# SCH_MinkyBoard_2025-11-26.net
KiCad netlist of a schematic drawn in EasyEDA
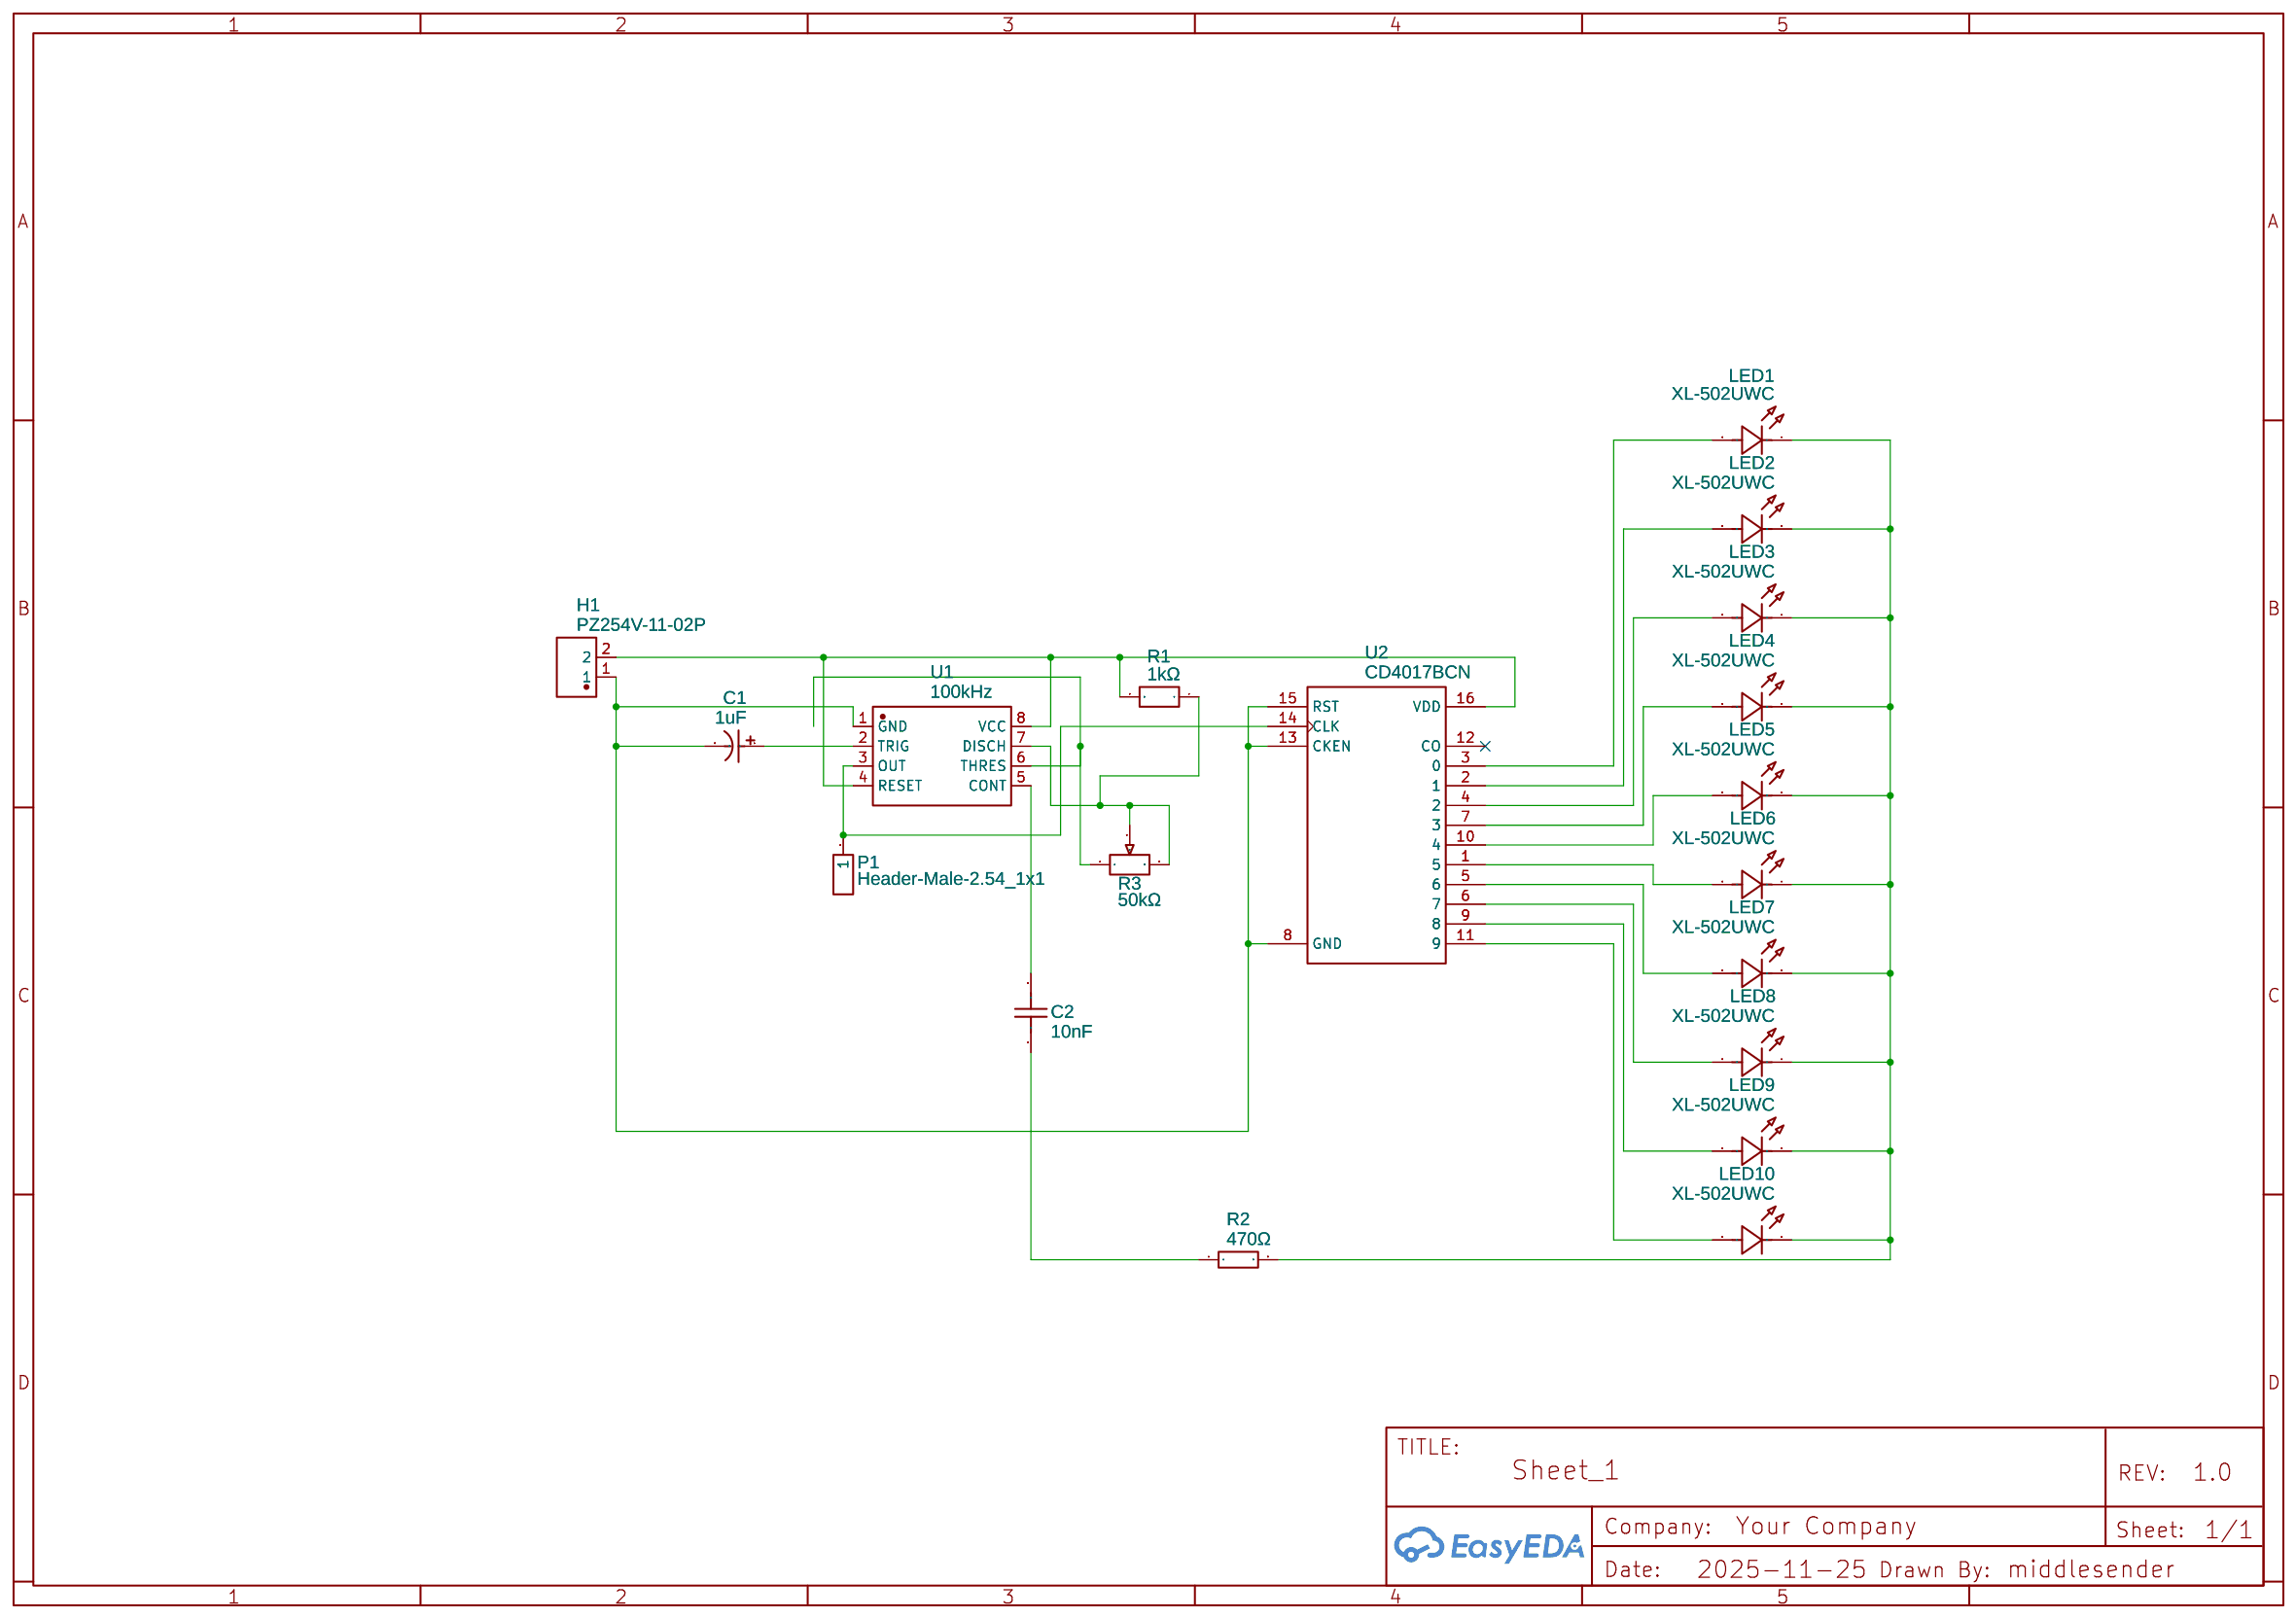
[diagram p0: schematic sheet]

(export (version "E")
  (design (tool "Eeschema 10.0.6"))
  (components
    (comp (ref "C1")
      (value "1uF")
      (fields (field (name "Manufacturer Part") "KF010M050C110A") (field (name "Manufacturer") "CapXon(丰宾)"))
      (libsource (lib "") (part "KF010M050C110A"))
    )
    (comp (ref "C2")
      (value "10nF")
      (fields (field (name "Manufacturer Part") "N09F1B103MN0B0S0N0") (field (name "Manufacturer") "STE(松田)"))
      (libsource (lib "") (part "N09F1B103MN0B0S0N0"))
    )
    (comp (ref "H1")
      (value "PZ254V-11-02P")
      (fields (field (name "Manufacturer") "XFCN(兴飞)"))
      (libsource (lib "") (part "PZ254V-11-02P"))
    )
    (comp (ref "LED1")
      (value "XL-502UWC")
      (fields (field (name "Manufacturer") "XINGLIGHT(成兴光)"))
      (libsource (lib "") (part "XL-502UWC"))
    )
    (comp (ref "LED2")
      (value "XL-502UWC")
      (fields (field (name "Manufacturer") "XINGLIGHT(成兴光)"))
      (libsource (lib "") (part "XL-502UWC"))
    )
    (comp (ref "LED3")
      (value "XL-502UWC")
      (fields (field (name "Manufacturer") "XINGLIGHT(成兴光)"))
      (libsource (lib "") (part "XL-502UWC"))
    )
    (comp (ref "LED4")
      (value "XL-502UWC")
      (fields (field (name "Manufacturer") "XINGLIGHT(成兴光)"))
      (libsource (lib "") (part "XL-502UWC"))
    )
    (comp (ref "LED5")
      (value "XL-502UWC")
      (fields (field (name "Manufacturer") "XINGLIGHT(成兴光)"))
      (libsource (lib "") (part "XL-502UWC"))
    )
    (comp (ref "LED6")
      (value "XL-502UWC")
      (fields (field (name "Manufacturer") "XINGLIGHT(成兴光)"))
      (libsource (lib "") (part "XL-502UWC"))
    )
    (comp (ref "LED7")
      (value "XL-502UWC")
      (fields (field (name "Manufacturer") "XINGLIGHT(成兴光)"))
      (libsource (lib "") (part "XL-502UWC"))
    )
    (comp (ref "LED8")
      (value "XL-502UWC")
      (fields (field (name "Manufacturer") "XINGLIGHT(成兴光)"))
      (libsource (lib "") (part "XL-502UWC"))
    )
    (comp (ref "LED9")
      (value "XL-502UWC")
      (fields (field (name "Manufacturer") "XINGLIGHT(成兴光)"))
      (libsource (lib "") (part "XL-502UWC"))
    )
    (comp (ref "LED10")
      (value "XL-502UWC")
      (fields (field (name "Manufacturer") "XINGLIGHT(成兴光)"))
      (libsource (lib "") (part "XL-502UWC"))
    )
    (comp (ref "P1")
      (value "Header-Male-2.54_1x1")
      (fields (field (name "Manufacturer Part") "2.54-1*1P针") (field (name "Manufacturer") "BOOMELE(博穆精密)"))
      (libsource (lib "") (part "Header-Male-2.54_1x1"))
    )
    (comp (ref "R1")
      (value "1kΩ")
      (fields (field (name "Manufacturer Part") "MF1/4W-1KΩ±1%T52") (field (name "Manufacturer") "华星机电"))
      (libsource (lib "") (part "MF1/4W-1KΩ±1%T52"))
    )
    (comp (ref "R2")
      (value "470Ω")
      (fields
        (field (name "Manufacturer Part") "MFR0W4F4700A50")
        (field (name "Manufacturer") "UNI-ROYAL(厚声)")
      )
      (libsource (lib "") (part "MFR0W4F4700A50"))
    )
    (comp (ref "R3")
      (value "50kΩ")
      (fields (field (name "Manufacturer Part") "3296X-1-503") (field (name "Manufacturer") "BOCHEN(博晨)"))
      (libsource (lib "") (part "3296X-1-503_C118912"))
    )
    (comp (ref "U1")
      (value "100kHz")
      (fields (field (name "Manufacturer Part") "NE555P") (field (name "Manufacturer") "TI(德州仪器)"))
      (libsource (lib "") (part "NE555P"))
    )
    (comp (ref "U2") (value "CD4017BCN") (libsource (lib "") (part "CD4017BCN")))
  )
  (nets
    (net (code "1") (name "Net-(C2-Pad1)") (class "Default")
      (node (ref "C2") (pin "1") (pinfunction "1_1") (pintype "unspecified"))
      (node (ref "R2") (pin "1") (pinfunction "1_1") (pintype "input"))
    )
    (net (code "2") (name "Net-(LED1-A)") (class "Default")
      (node (ref "LED1") (pin "2") (pinfunction "A_2") (pintype "unspecified"))
      (node (ref "U2") (pin "3") (pinfunction "0_3") (pintype "output"))
    )
    (net (code "3") (name "Net-(LED1-K)") (class "Default")
      (node (ref "LED1") (pin "1") (pinfunction "K_1") (pintype "unspecified"))
      (node (ref "LED10") (pin "1") (pinfunction "K_1") (pintype "unspecified"))
      (node (ref "LED2") (pin "1") (pinfunction "K_1") (pintype "unspecified"))
      (node (ref "LED3") (pin "1") (pinfunction "K_1") (pintype "unspecified"))
      (node (ref "LED4") (pin "1") (pinfunction "K_1") (pintype "unspecified"))
      (node (ref "LED5") (pin "1") (pinfunction "K_1") (pintype "unspecified"))
      (node (ref "LED6") (pin "1") (pinfunction "K_1") (pintype "unspecified"))
      (node (ref "LED7") (pin "1") (pinfunction "K_1") (pintype "unspecified"))
      (node (ref "LED8") (pin "1") (pinfunction "K_1") (pintype "unspecified"))
      (node (ref "LED9") (pin "1") (pinfunction "K_1") (pintype "unspecified"))
      (node (ref "R2") (pin "2") (pinfunction "2_2") (pintype "input"))
    )
    (net (code "4") (name "Net-(LED2-A)") (class "Default")
      (node (ref "LED2") (pin "2") (pinfunction "A_2") (pintype "unspecified"))
      (node (ref "U2") (pin "2") (pinfunction "1_2") (pintype "output"))
    )
    (net (code "5") (name "Net-(LED3-A)") (class "Default")
      (node (ref "LED3") (pin "2") (pinfunction "A_2") (pintype "unspecified"))
      (node (ref "U2") (pin "4") (pinfunction "2_4") (pintype "output"))
    )
    (net (code "6") (name "Net-(LED4-A)") (class "Default")
      (node (ref "LED4") (pin "2") (pinfunction "A_2") (pintype "unspecified"))
      (node (ref "U2") (pin "7") (pinfunction "3_7") (pintype "output"))
    )
    (net (code "7") (name "Net-(LED5-A)") (class "Default")
      (node (ref "LED5") (pin "2") (pinfunction "A_2") (pintype "unspecified"))
      (node (ref "U2") (pin "10") (pinfunction "4_10") (pintype "output"))
    )
    (net (code "8") (name "Net-(LED6-A)") (class "Default")
      (node (ref "LED6") (pin "2") (pinfunction "A_2") (pintype "unspecified"))
      (node (ref "U2") (pin "1") (pinfunction "5_1") (pintype "output"))
    )
    (net (code "9") (name "Net-(LED7-A)") (class "Default")
      (node (ref "LED7") (pin "2") (pinfunction "A_2") (pintype "unspecified"))
      (node (ref "U2") (pin "5") (pinfunction "6_5") (pintype "output"))
    )
    (net (code "10") (name "Net-(LED8-A)") (class "Default")
      (node (ref "LED8") (pin "2") (pinfunction "A_2") (pintype "unspecified"))
      (node (ref "U2") (pin "6") (pinfunction "7_6") (pintype "output"))
    )
    (net (code "11") (name "Net-(LED9-A)") (class "Default")
      (node (ref "LED9") (pin "2") (pinfunction "A_2") (pintype "unspecified"))
      (node (ref "U2") (pin "9") (pinfunction "8_9") (pintype "output"))
    )
    (net (code "12") (name "Net-(LED10-A)") (class "Default")
      (node (ref "LED10") (pin "2") (pinfunction "A_2") (pintype "unspecified"))
      (node (ref "U2") (pin "11") (pinfunction "9_11") (pintype "output"))
    )
    (net (code "13") (name "Net-(U1-CONT)") (class "Default")
      (node (ref "C2") (pin "2") (pinfunction "2_2") (pintype "unspecified"))
      (node (ref "U1") (pin "5") (pinfunction "CONT_5") (pintype "unspecified"))
    )
    (net (code "14") (name "Net-(U1-DISCH)") (class "Default")
      (node (ref "R1") (pin "1") (pinfunction "1_1") (pintype "unspecified"))
      (node (ref "R3") (pin "2") (pinfunction "2_2") (pintype "input"))
      (node (ref "R3") (pin "3") (pinfunction "3_3") (pintype "input"))
      (node (ref "U1") (pin "7") (pinfunction "DISCH_7") (pintype "unspecified"))
    )
    (net (code "15") (name "Net-(U1-GND)") (class "Default")
      (node (ref "C1") (pin "2") (pinfunction "2_2") (pintype "input"))
      (node (ref "H1") (pin "1") (pinfunction "1_1") (pintype "unspecified"))
      (node (ref "U1") (pin "1") (pinfunction "GND_1") (pintype "unspecified"))
      (node (ref "U2") (pin "13") (pinfunction "CKEN_13") (pintype "unspecified"))
      (node (ref "U2") (pin "15") (pinfunction "RST_15") (pintype "unspecified"))
      (node (ref "U2") (pin "8") (pinfunction "GND_8") (pintype "passive"))
    )
    (net (code "16") (name "Net-(U1-OUT)") (class "Default")
      (node (ref "P1") (pin "1") (pinfunction "1_1") (pintype "input"))
      (node (ref "U1") (pin "3") (pinfunction "OUT_3") (pintype "unspecified"))
      (node (ref "U2") (pin "14") (pinfunction "CLK_14") (pintype "unspecified"))
    )
    (net (code "17") (name "Net-(U1-RESET)") (class "Default")
      (node (ref "H1") (pin "2") (pinfunction "2_2") (pintype "unspecified"))
      (node (ref "R1") (pin "2") (pinfunction "2_2") (pintype "unspecified"))
      (node (ref "U1") (pin "4") (pinfunction "RESET_4") (pintype "unspecified"))
      (node (ref "U1") (pin "8") (pinfunction "VCC_8") (pintype "unspecified"))
      (node (ref "U2") (pin "16") (pinfunction "VDD_16") (pintype "passive"))
    )
    (net (code "18") (name "Net-(U1-THRES)") (class "Default")
      (node (ref "R3") (pin "1") (pinfunction "1_1") (pintype "input"))
      (node (ref "U1") (pin "6") (pinfunction "THRES_6") (pintype "unspecified"))
    )
    (net (code "19") (name "Net-(U1-TRIG)") (class "Default")
      (node (ref "C1") (pin "1") (pinfunction "1_1") (pintype "input"))
      (node (ref "U1") (pin "2") (pinfunction "TRIG_2") (pintype "unspecified"))
    )
    (net (code "20") (name "unconnected-(U2-CO-Pad12)") (class "Default")
      (node (ref "U2") (pin "12") (pinfunction "CO_12") (pintype "output+no_connect"))
    )
  )
)
